# ORing_block.net
KiCad netlist of a schematic drawn in EAGLE
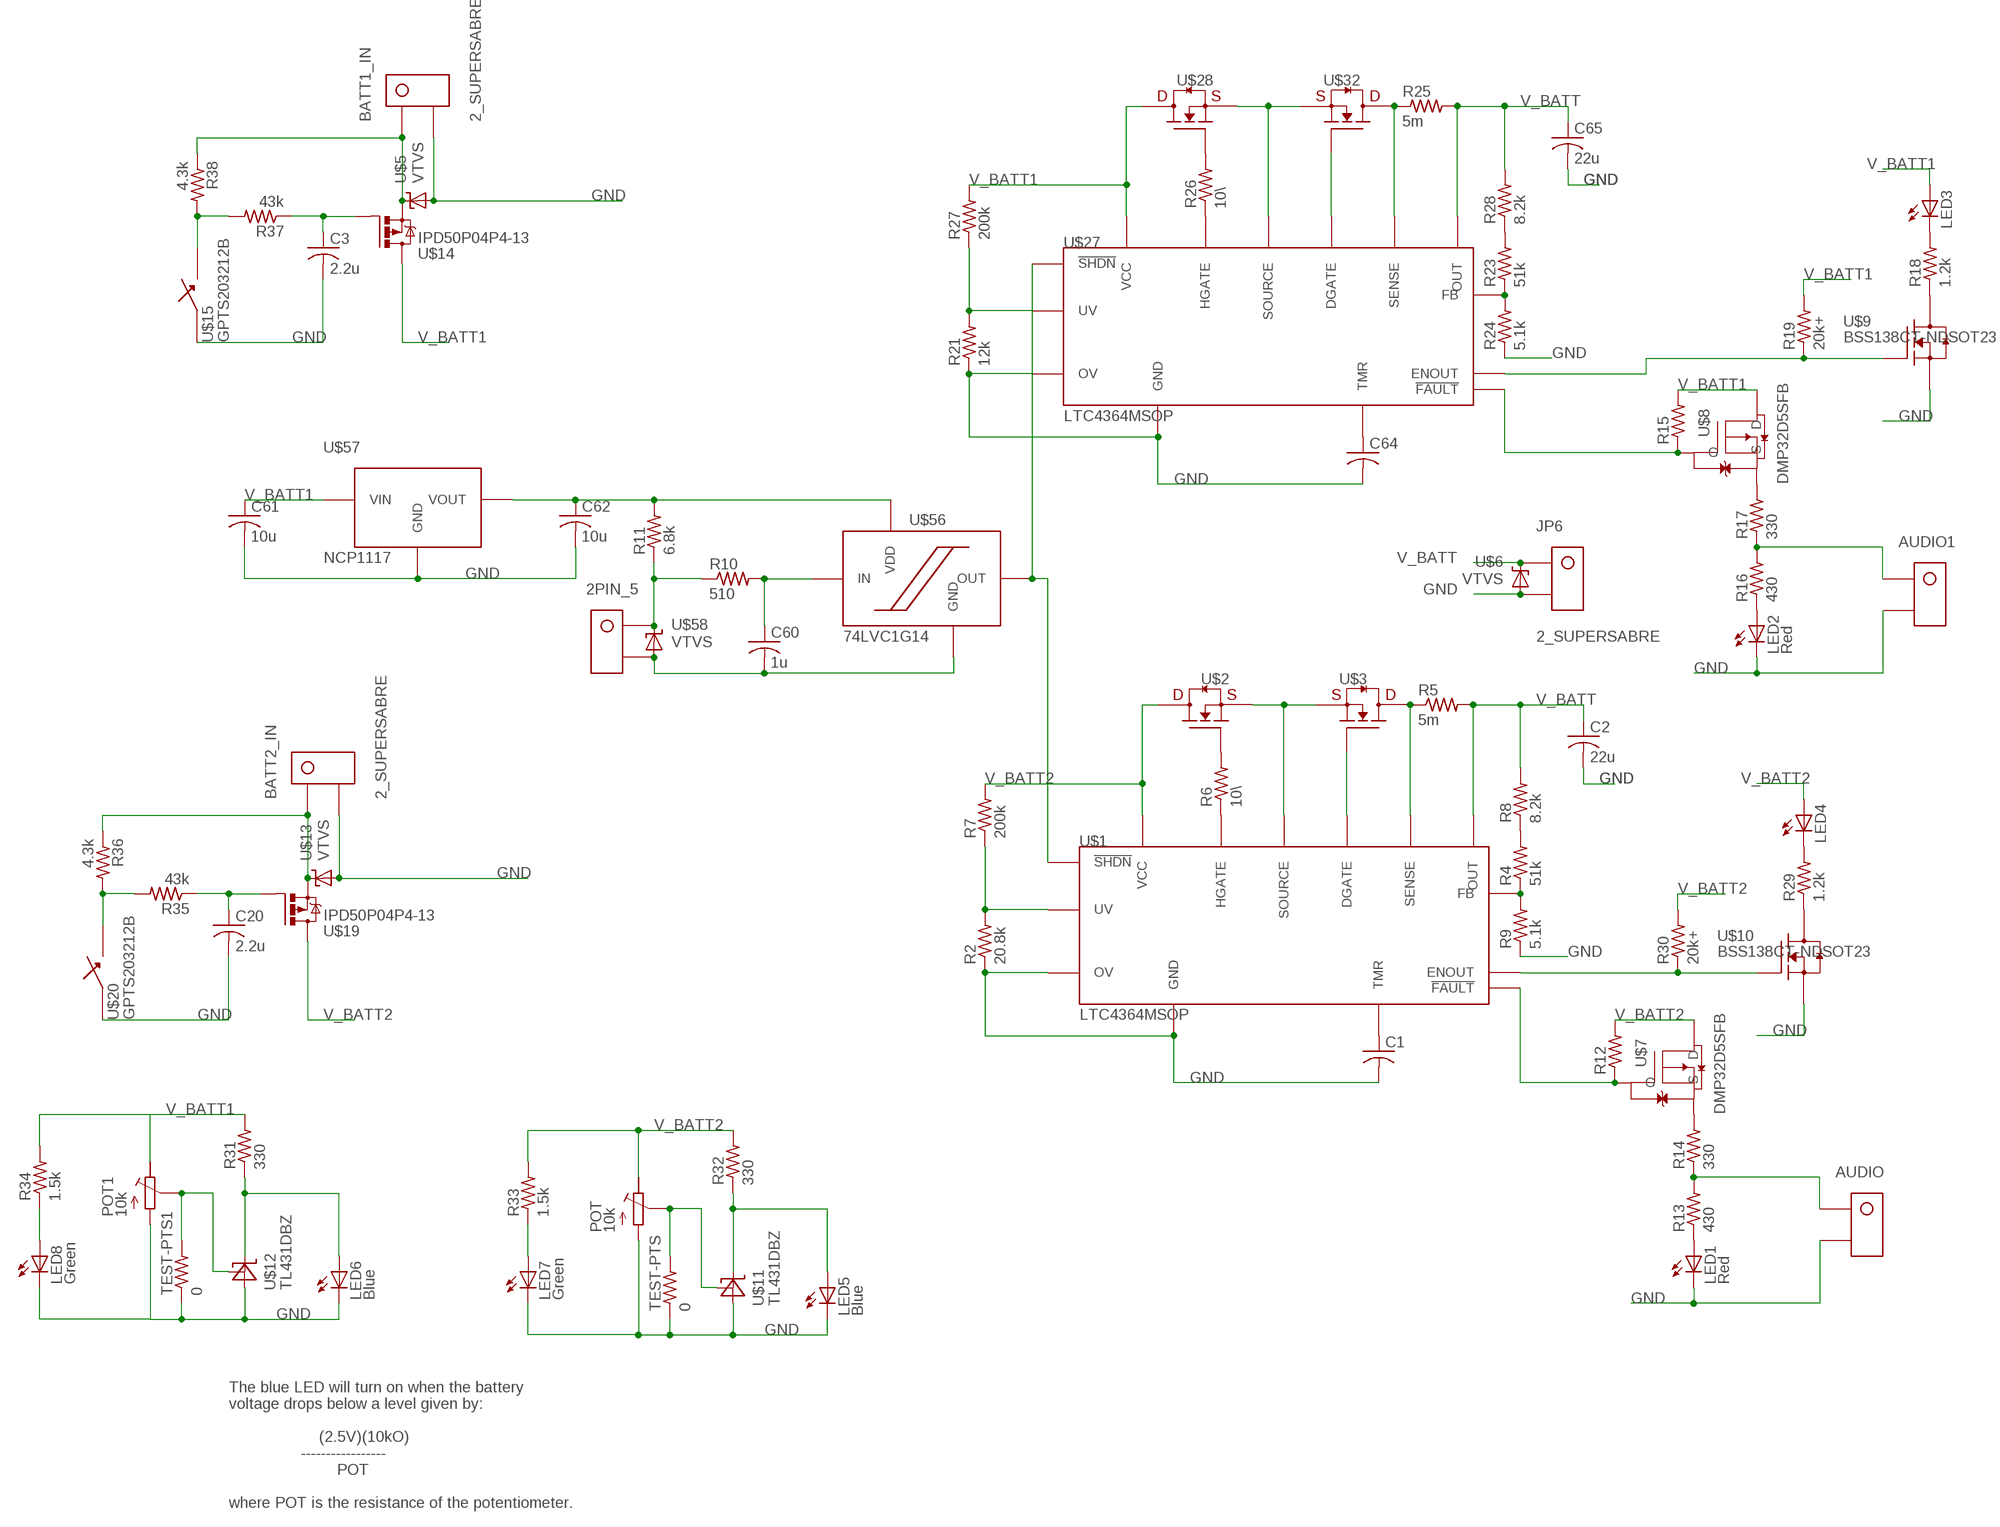
[diagram p0: schematic, sheet 1]

(export (version "E")
  (design (tool "Eeschema 10.0.6"))
  (components
    (comp (ref "2PIN_5")
      (value "KK254_VERT_2PIN22-29-2021")
      (footprint "eagle-import:KK254_VERT_2PIN")
      (libsource (lib "eagle-import") (part "KK254_VERT_2PIN22-29-2021"))
    )
    (comp (ref "AUDIO")
      (value "KK254_VERT_2PIN22-29-2021")
      (footprint "eagle-import:KK254_VERT_2PIN")
      (libsource (lib "eagle-import") (part "KK254_VERT_2PIN22-29-2021"))
    )
    (comp (ref "AUDIO1")
      (value "KK254_VERT_2PIN22-29-2021")
      (footprint "eagle-import:KK254_VERT_2PIN")
      (libsource (lib "eagle-import") (part "KK254_VERT_2PIN22-29-2021"))
    )
    (comp (ref "BATT1_IN")
      (value "2_SUPERSABRE")
      (footprint "eagle-import:SUPERSABRE_2CIRCUIT")
      (libsource (lib "eagle-import") (part "2_SUPERSABRE"))
    )
    (comp (ref "BATT2_IN")
      (value "2_SUPERSABRE")
      (footprint "eagle-import:SUPERSABRE_2CIRCUIT")
      (libsource (lib "eagle-import") (part "2_SUPERSABRE"))
    )
    (comp (ref "C1")
      (value "C-USC0805")
      (footprint "eagle-import:C0805")
      (libsource (lib "eagle-import") (part "C-USC0805"))
    )
    (comp (ref "C2")
      (value "22u")
      (footprint "eagle-import:C0805")
      (libsource (lib "eagle-import") (part "C-USC0805"))
    )
    (comp (ref "C3")
      (value "2.2u")
      (footprint "eagle-import:C0805")
      (libsource (lib "eagle-import") (part "C-USC0805"))
    )
    (comp (ref "C20")
      (value "2.2u")
      (footprint "eagle-import:C0805")
      (libsource (lib "eagle-import") (part "C-USC0805"))
    )
    (comp (ref "C60")
      (value "1u")
      (footprint "eagle-import:C0805")
      (libsource (lib "eagle-import") (part "C-USC0805"))
    )
    (comp (ref "C61")
      (value "10u")
      (footprint "eagle-import:C0805")
      (libsource (lib "eagle-import") (part "C-USC0805"))
    )
    (comp (ref "C62")
      (value "10u")
      (footprint "eagle-import:C0805")
      (libsource (lib "eagle-import") (part "C-USC0805"))
    )
    (comp (ref "C64")
      (value "C-USC0805")
      (footprint "eagle-import:C0805")
      (libsource (lib "eagle-import") (part "C-USC0805"))
    )
    (comp (ref "C65")
      (value "22u")
      (footprint "eagle-import:C0805")
      (libsource (lib "eagle-import") (part "C-USC0805"))
    )
    (comp (ref "JP6")
      (value "2_SUPERSABRE")
      (footprint "eagle-import:SUPERSABRE_2CIRCUIT")
      (libsource (lib "eagle-import") (part "2_SUPERSABRE"))
    )
    (comp (ref "LED1")
      (value "Red")
      (footprint "eagle-import:CHIPLED_0805")
      (libsource (lib "eagle-import") (part "LEDCHIPLED_0805"))
    )
    (comp (ref "LED2")
      (value "Red")
      (footprint "eagle-import:CHIPLED_0805")
      (libsource (lib "eagle-import") (part "LEDCHIPLED_0805"))
    )
    (comp (ref "LED3")
      (value "LEDCHIPLED_0805")
      (footprint "eagle-import:CHIPLED_0805")
      (libsource (lib "eagle-import") (part "LEDCHIPLED_0805"))
    )
    (comp (ref "LED4")
      (value "LEDCHIPLED_0805")
      (footprint "eagle-import:CHIPLED_0805")
      (libsource (lib "eagle-import") (part "LEDCHIPLED_0805"))
    )
    (comp (ref "LED5")
      (value "Blue")
      (footprint "eagle-import:0805")
      (libsource (lib "eagle-import") (part "0805_LED"))
    )
    (comp (ref "LED6")
      (value "Blue")
      (footprint "eagle-import:0805")
      (libsource (lib "eagle-import") (part "0805_LED"))
    )
    (comp (ref "LED7")
      (value "Green")
      (footprint "eagle-import:0805")
      (libsource (lib "eagle-import") (part "0805_LED"))
    )
    (comp (ref "LED8")
      (value "Green")
      (footprint "eagle-import:0805")
      (libsource (lib "eagle-import") (part "0805_LED"))
    )
    (comp (ref "POT")
      (value "10k")
      (footprint "eagle-import:PTV09A-4")
      (libsource (lib "eagle-import") (part "R-TRIMMPTV09A-4"))
    )
    (comp (ref "POT1")
      (value "10k")
      (footprint "eagle-import:PTV09A-4")
      (libsource (lib "eagle-import") (part "R-TRIMMPTV09A-4"))
    )
    (comp (ref "R2")
      (value "20.8k")
      (footprint "eagle-import:R0805")
      (libsource (lib "eagle-import") (part "R-US_R0805"))
    )
    (comp (ref "R4")
      (value "51k")
      (footprint "eagle-import:R0805")
      (libsource (lib "eagle-import") (part "R-US_R0805"))
    )
    (comp (ref "R5")
      (value "5m")
      (footprint "eagle-import:R0805")
      (libsource (lib "eagle-import") (part "R-US_R0805"))
    )
    (comp (ref "R6")
      (value "10\\")
      (footprint "eagle-import:R0805")
      (libsource (lib "eagle-import") (part "R-US_R0805"))
    )
    (comp (ref "R7")
      (value "200k")
      (footprint "eagle-import:R0805")
      (libsource (lib "eagle-import") (part "R-US_R0805"))
    )
    (comp (ref "R8")
      (value "8.2k")
      (footprint "eagle-import:R0805")
      (libsource (lib "eagle-import") (part "R-US_R0805"))
    )
    (comp (ref "R9")
      (value "5.1k")
      (footprint "eagle-import:R0805")
      (libsource (lib "eagle-import") (part "R-US_R0805"))
    )
    (comp (ref "R10")
      (value "510")
      (footprint "eagle-import:R0805")
      (libsource (lib "eagle-import") (part "R-US_R0805"))
    )
    (comp (ref "R11")
      (value "6.8k")
      (footprint "eagle-import:R0805")
      (libsource (lib "eagle-import") (part "R-US_R0805"))
    )
    (comp (ref "R12")
      (value "R-US_R0805")
      (footprint "eagle-import:R0805")
      (libsource (lib "eagle-import") (part "R-US_R0805"))
    )
    (comp (ref "R13")
      (value "430")
      (footprint "eagle-import:R0805")
      (libsource (lib "eagle-import") (part "R-US_R0805"))
    )
    (comp (ref "R14")
      (value "330")
      (footprint "eagle-import:R0805")
      (libsource (lib "eagle-import") (part "R-US_R0805"))
    )
    (comp (ref "R15")
      (value "R-US_R0805")
      (footprint "eagle-import:R0805")
      (libsource (lib "eagle-import") (part "R-US_R0805"))
    )
    (comp (ref "R16")
      (value "430")
      (footprint "eagle-import:R0805")
      (libsource (lib "eagle-import") (part "R-US_R0805"))
    )
    (comp (ref "R17")
      (value "330")
      (footprint "eagle-import:R0805")
      (libsource (lib "eagle-import") (part "R-US_R0805"))
    )
    (comp (ref "R18")
      (value "1.2k")
      (footprint "eagle-import:R0805")
      (libsource (lib "eagle-import") (part "R-US_R0805"))
    )
    (comp (ref "R19")
      (value "20k+")
      (footprint "eagle-import:R0805")
      (libsource (lib "eagle-import") (part "R-US_R0805"))
    )
    (comp (ref "R21")
      (value "12k")
      (footprint "eagle-import:R0805")
      (libsource (lib "eagle-import") (part "R-US_R0805"))
    )
    (comp (ref "R23")
      (value "51k")
      (footprint "eagle-import:R0805")
      (libsource (lib "eagle-import") (part "R-US_R0805"))
    )
    (comp (ref "R24")
      (value "5.1k")
      (footprint "eagle-import:R0805")
      (libsource (lib "eagle-import") (part "R-US_R0805"))
    )
    (comp (ref "R25")
      (value "5m")
      (footprint "eagle-import:R0805")
      (libsource (lib "eagle-import") (part "R-US_R0805"))
    )
    (comp (ref "R26")
      (value "10\\")
      (footprint "eagle-import:R0805")
      (libsource (lib "eagle-import") (part "R-US_R0805"))
    )
    (comp (ref "R27")
      (value "200k")
      (footprint "eagle-import:R0805")
      (libsource (lib "eagle-import") (part "R-US_R0805"))
    )
    (comp (ref "R28")
      (value "8.2k")
      (footprint "eagle-import:R0805")
      (libsource (lib "eagle-import") (part "R-US_R0805"))
    )
    (comp (ref "R29")
      (value "1.2k")
      (footprint "eagle-import:R0805")
      (libsource (lib "eagle-import") (part "R-US_R0805"))
    )
    (comp (ref "R30")
      (value "20k+")
      (footprint "eagle-import:R0805")
      (libsource (lib "eagle-import") (part "R-US_R0805"))
    )
    (comp (ref "R31")
      (value "330")
      (footprint "eagle-import:R0805")
      (libsource (lib "eagle-import") (part "R-US_R0805"))
    )
    (comp (ref "R32")
      (value "330")
      (footprint "eagle-import:R0805")
      (libsource (lib "eagle-import") (part "R-US_R0805"))
    )
    (comp (ref "R33")
      (value "1.5k")
      (footprint "eagle-import:R0805")
      (libsource (lib "eagle-import") (part "R-US_R0805"))
    )
    (comp (ref "R34")
      (value "1.5k")
      (footprint "eagle-import:R0805")
      (libsource (lib "eagle-import") (part "R-US_R0805"))
    )
    (comp (ref "R35")
      (value "43k")
      (footprint "eagle-import:R0805")
      (libsource (lib "eagle-import") (part "R-US_R0805"))
    )
    (comp (ref "R36")
      (value "4.3k")
      (footprint "eagle-import:R0805")
      (libsource (lib "eagle-import") (part "R-US_R0805"))
    )
    (comp (ref "R37")
      (value "43k")
      (footprint "eagle-import:R0805")
      (libsource (lib "eagle-import") (part "R-US_R0805"))
    )
    (comp (ref "R38")
      (value "4.3k")
      (footprint "eagle-import:R0805")
      (libsource (lib "eagle-import") (part "R-US_R0805"))
    )
    (comp (ref "TEST-PTS")
      (value "0")
      (footprint "eagle-import:V526-0")
      (libsource (lib "eagle-import") (part "R-US_V526-0"))
    )
    (comp (ref "TEST-PTS1")
      (value "0")
      (footprint "eagle-import:V526-0")
      (libsource (lib "eagle-import") (part "R-US_V526-0"))
    )
    (comp (ref "U$1")
      (value "LTC4364MSOP")
      (footprint "eagle-import:MSOP16")
      (libsource (lib "eagle-import") (part "LTC4364MSOP"))
    )
    (comp (ref "U$2")
      (value "FDMC8360LET40PWR33")
      (footprint "eagle-import:POWER33")
      (libsource (lib "eagle-import") (part "FDMC8360LET40PWR33"))
    )
    (comp (ref "U$3")
      (value "FDMC8360LET40PWR33")
      (footprint "eagle-import:POWER33")
      (libsource (lib "eagle-import") (part "FDMC8360LET40PWR33"))
    )
    (comp (ref "U$5")
      (value "VTVS")
      (footprint "eagle-import:DO-219AB")
      (libsource (lib "eagle-import") (part "VTVS"))
    )
    (comp (ref "U$6")
      (value "VTVS")
      (footprint "eagle-import:DO-219AB")
      (libsource (lib "eagle-import") (part "VTVS"))
    )
    (comp (ref "U$7")
      (value "DMP32D5SFB")
      (footprint "eagle-import:AP02002")
      (libsource (lib "eagle-import") (part "DMP32D5SFB"))
    )
    (comp (ref "U$8")
      (value "DMP32D5SFB")
      (footprint "eagle-import:AP02002")
      (libsource (lib "eagle-import") (part "DMP32D5SFB"))
    )
    (comp (ref "U$9")
      (value "BSS138CT-NDSOT23")
      (footprint "eagle-import:SOT23")
      (libsource (lib "eagle-import") (part "BSS138CT-NDSOT23"))
    )
    (comp (ref "U$10")
      (value "BSS138CT-NDSOT23")
      (footprint "eagle-import:SOT23")
      (libsource (lib "eagle-import") (part "BSS138CT-NDSOT23"))
    )
    (comp (ref "U$11")
      (value "TL431DBZ")
      (footprint "eagle-import:SOT-23-3")
      (libsource (lib "eagle-import") (part "TL431DBZ"))
    )
    (comp (ref "U$12")
      (value "TL431DBZ")
      (footprint "eagle-import:SOT-23-3")
      (libsource (lib "eagle-import") (part "TL431DBZ"))
    )
    (comp (ref "U$13")
      (value "VTVS")
      (footprint "eagle-import:DO-219AB")
      (libsource (lib "eagle-import") (part "VTVS"))
    )
    (comp (ref "U$14")
      (value "IPD50P04P4-13")
      (footprint "eagle-import:TO252-3")
      (libsource (lib "eagle-import") (part "IPD50P04P4-13"))
    )
    (comp (ref "U$15")
      (value "GPTS203212B")
      (footprint "eagle-import:GPTS203211B")
      (libsource (lib "eagle-import") (part "GPTS203212B"))
    )
    (comp (ref "U$19")
      (value "IPD50P04P4-13")
      (footprint "eagle-import:TO252-3")
      (libsource (lib "eagle-import") (part "IPD50P04P4-13"))
    )
    (comp (ref "U$20")
      (value "GPTS203212B")
      (footprint "eagle-import:GPTS203211B")
      (libsource (lib "eagle-import") (part "GPTS203212B"))
    )
    (comp (ref "U$27")
      (value "LTC4364MSOP")
      (footprint "eagle-import:MSOP16")
      (libsource (lib "eagle-import") (part "LTC4364MSOP"))
    )
    (comp (ref "U$28")
      (value "FDMC8360LET40PWR33")
      (footprint "eagle-import:POWER33")
      (libsource (lib "eagle-import") (part "FDMC8360LET40PWR33"))
    )
    (comp (ref "U$32")
      (value "FDMC8360LET40PWR33")
      (footprint "eagle-import:POWER33")
      (libsource (lib "eagle-import") (part "FDMC8360LET40PWR33"))
    )
    (comp (ref "U$56")
      (value "74LVC1G14")
      (footprint "eagle-import:TSSOP5")
      (libsource (lib "eagle-import") (part "74LVC1G14"))
    )
    (comp (ref "U$57")
      (value "NCP1117")
      (footprint "eagle-import:SOT-223")
      (libsource (lib "eagle-import") (part "NCP1117"))
    )
    (comp (ref "U$58")
      (value "VTVS")
      (footprint "eagle-import:DO-219AB")
      (libsource (lib "eagle-import") (part "VTVS"))
    )
  )
  (nets
    (net (code "1") (name "/GND") (class "Default")
      (node (ref "AUDIO") (pin "P$2") (pinfunction "P$2_P$2") (pintype "bidirectional"))
      (node (ref "AUDIO1") (pin "P$2") (pinfunction "P$2_P$2") (pintype "bidirectional"))
      (node (ref "BATT1_IN") (pin "P$2") (pinfunction "P$2_P$2") (pintype "bidirectional"))
      (node (ref "BATT2_IN") (pin "P$2") (pinfunction "P$2_P$2") (pintype "bidirectional"))
      (node (ref "C1") (pin "2") (pinfunction "2_2") (pintype "passive"))
      (node (ref "C2") (pin "2") (pinfunction "2_2") (pintype "passive"))
      (node (ref "C20") (pin "2") (pinfunction "2_2") (pintype "passive"))
      (node (ref "C3") (pin "2") (pinfunction "2_2") (pintype "passive"))
      (node (ref "C61") (pin "2") (pinfunction "2_2") (pintype "passive"))
      (node (ref "C62") (pin "2") (pinfunction "2_2") (pintype "passive"))
      (node (ref "C64") (pin "2") (pinfunction "2_2") (pintype "passive"))
      (node (ref "C65") (pin "2") (pinfunction "2_2") (pintype "passive"))
      (node (ref "JP6") (pin "P$2") (pinfunction "P$2_P$2") (pintype "bidirectional"))
      (node (ref "LED1") (pin "C") (pinfunction "C_C") (pintype "passive"))
      (node (ref "LED2") (pin "C") (pinfunction "C_C") (pintype "passive"))
      (node (ref "LED5") (pin "P$2") (pinfunction "C_P$2") (pintype "passive"))
      (node (ref "LED6") (pin "P$2") (pinfunction "C_P$2") (pintype "passive"))
      (node (ref "LED7") (pin "P$2") (pinfunction "C_P$2") (pintype "passive"))
      (node (ref "LED8") (pin "P$2") (pinfunction "C_P$2") (pintype "passive"))
      (node (ref "POT") (pin "P$3") (pinfunction "E_P$3") (pintype "passive"))
      (node (ref "POT1") (pin "P$3") (pinfunction "E_P$3") (pintype "passive"))
      (node (ref "R2") (pin "1") (pinfunction "1_1") (pintype "passive"))
      (node (ref "R21") (pin "1") (pinfunction "1_1") (pintype "passive"))
      (node (ref "R24") (pin "1") (pinfunction "1_1") (pintype "passive"))
      (node (ref "R9") (pin "1") (pinfunction "1_1") (pintype "passive"))
      (node (ref "TEST-PTS") (pin "1") (pinfunction "1_1") (pintype "passive"))
      (node (ref "TEST-PTS1") (pin "1") (pinfunction "1_1") (pintype "passive"))
      (node (ref "U$1") (pin "GND") (pinfunction "GND_GND") (pintype "bidirectional"))
      (node (ref "U$1") (pin "OV") (pinfunction "OV_OV") (pintype "bidirectional"))
      (node (ref "U$10") (pin "2") (pinfunction "S_2") (pintype "passive"))
      (node (ref "U$11") (pin "P$3") (pinfunction "A_P$3") (pintype "passive"))
      (node (ref "U$12") (pin "P$3") (pinfunction "A_P$3") (pintype "passive"))
      (node (ref "U$13") (pin "P$1") (pinfunction "A_P$1") (pintype "passive"))
      (node (ref "U$15") (pin "P$1") (pinfunction "P$1_P$1") (pintype "bidirectional"))
      (node (ref "U$20") (pin "P$1") (pinfunction "P$1_P$1") (pintype "bidirectional"))
      (node (ref "U$27") (pin "GND") (pinfunction "GND_GND") (pintype "bidirectional"))
      (node (ref "U$27") (pin "OV") (pinfunction "OV_OV") (pintype "bidirectional"))
      (node (ref "U$5") (pin "P$1") (pinfunction "A_P$1") (pintype "passive"))
      (node (ref "U$57") (pin "P$1") (pinfunction "GND_P$1") (pintype "bidirectional"))
      (node (ref "U$6") (pin "P$1") (pinfunction "A_P$1") (pintype "passive"))
      (node (ref "U$9") (pin "2") (pinfunction "S_2") (pintype "passive"))
    )
    (net (code "2") (name "/V_BATT") (class "Default")
      (node (ref "C2") (pin "1") (pinfunction "1_1") (pintype "passive"))
      (node (ref "C65") (pin "1") (pinfunction "1_1") (pintype "passive"))
      (node (ref "JP6") (pin "P$1") (pinfunction "P$1_P$1") (pintype "bidirectional"))
      (node (ref "R25") (pin "2") (pinfunction "2_2") (pintype "passive"))
      (node (ref "R28") (pin "2") (pinfunction "2_2") (pintype "passive"))
      (node (ref "R5") (pin "2") (pinfunction "2_2") (pintype "passive"))
      (node (ref "R8") (pin "2") (pinfunction "2_2") (pintype "passive"))
      (node (ref "U$1") (pin "OUT") (pinfunction "OUT_OUT") (pintype "bidirectional"))
      (node (ref "U$27") (pin "OUT") (pinfunction "OUT_OUT") (pintype "bidirectional"))
      (node (ref "U$6") (pin "P$2") (pinfunction "C_P$2") (pintype "passive"))
    )
    (net (code "3") (name "/V_BATT1") (class "Default")
      (node (ref "C61") (pin "1") (pinfunction "1_1") (pintype "passive"))
      (node (ref "LED3") (pin "A") (pinfunction "A_A") (pintype "passive"))
      (node (ref "POT1") (pin "P$1") (pinfunction "A_P$1") (pintype "passive"))
      (node (ref "R15") (pin "2") (pinfunction "2_2") (pintype "passive"))
      (node (ref "R19") (pin "2") (pinfunction "2_2") (pintype "passive"))
      (node (ref "R27") (pin "2") (pinfunction "2_2") (pintype "passive"))
      (node (ref "R31") (pin "2") (pinfunction "2_2") (pintype "passive"))
      (node (ref "R34") (pin "2") (pinfunction "2_2") (pintype "passive"))
      (node (ref "U$14") (pin "3") (pinfunction "S_3") (pintype "passive"))
      (node (ref "U$27") (pin "VCC") (pinfunction "VCC_VCC") (pintype "bidirectional"))
      (node (ref "U$28") (pin "DRAIN") (pinfunction "DRAIN_DRAIN") (pintype "bidirectional"))
      (node (ref "U$57") (pin "P$3") (pinfunction "VIN_P$3") (pintype "bidirectional"))
      (node (ref "U$8") (pin "P$3") (pinfunction "D_P$3") (pintype "bidirectional"))
    )
    (net (code "4") (name "/V_BATT2") (class "Default")
      (node (ref "LED4") (pin "A") (pinfunction "A_A") (pintype "passive"))
      (node (ref "POT") (pin "P$1") (pinfunction "A_P$1") (pintype "passive"))
      (node (ref "R12") (pin "2") (pinfunction "2_2") (pintype "passive"))
      (node (ref "R30") (pin "2") (pinfunction "2_2") (pintype "passive"))
      (node (ref "R32") (pin "2") (pinfunction "2_2") (pintype "passive"))
      (node (ref "R33") (pin "2") (pinfunction "2_2") (pintype "passive"))
      (node (ref "R7") (pin "2") (pinfunction "2_2") (pintype "passive"))
      (node (ref "U$1") (pin "VCC") (pinfunction "VCC_VCC") (pintype "bidirectional"))
      (node (ref "U$19") (pin "3") (pinfunction "S_3") (pintype "passive"))
      (node (ref "U$2") (pin "DRAIN") (pinfunction "DRAIN_DRAIN") (pintype "bidirectional"))
      (node (ref "U$7") (pin "P$3") (pinfunction "D_P$3") (pintype "bidirectional"))
    )
    (net (code "5") (name "Net-(AUDIO-PadP$1)") (class "Default")
      (node (ref "AUDIO") (pin "P$1") (pinfunction "P$1_P$1") (pintype "bidirectional"))
      (node (ref "R13") (pin "2") (pinfunction "2_2") (pintype "passive"))
      (node (ref "R14") (pin "1") (pinfunction "1_1") (pintype "passive"))
    )
    (net (code "6") (name "Net-(AUDIO1-PadP$1)") (class "Default")
      (node (ref "AUDIO1") (pin "P$1") (pinfunction "P$1_P$1") (pintype "bidirectional"))
      (node (ref "R16") (pin "2") (pinfunction "2_2") (pintype "passive"))
      (node (ref "R17") (pin "1") (pinfunction "1_1") (pintype "passive"))
    )
    (net (code "7") (name "Net-(C1-Pad1)") (class "Default")
      (node (ref "C1") (pin "1") (pinfunction "1_1") (pintype "passive"))
      (node (ref "U$1") (pin "TMR") (pinfunction "TMR_TMR") (pintype "bidirectional"))
    )
    (net (code "8") (name "Net-(C64-Pad1)") (class "Default")
      (node (ref "C64") (pin "1") (pinfunction "1_1") (pintype "passive"))
      (node (ref "U$27") (pin "TMR") (pinfunction "TMR_TMR") (pintype "bidirectional"))
    )
    (net (code "9") (name "Net-(LED1-PadA)") (class "Default")
      (node (ref "LED1") (pin "A") (pinfunction "A_A") (pintype "passive"))
      (node (ref "R13") (pin "1") (pinfunction "1_1") (pintype "passive"))
    )
    (net (code "10") (name "Net-(LED2-PadA)") (class "Default")
      (node (ref "LED2") (pin "A") (pinfunction "A_A") (pintype "passive"))
      (node (ref "R16") (pin "1") (pinfunction "1_1") (pintype "passive"))
    )
    (net (code "11") (name "Net-(LED3-PadC)") (class "Default")
      (node (ref "LED3") (pin "C") (pinfunction "C_C") (pintype "passive"))
      (node (ref "R18") (pin "2") (pinfunction "2_2") (pintype "passive"))
    )
    (net (code "12") (name "Net-(LED4-PadC)") (class "Default")
      (node (ref "LED4") (pin "C") (pinfunction "C_C") (pintype "passive"))
      (node (ref "R29") (pin "2") (pinfunction "2_2") (pintype "passive"))
    )
    (net (code "13") (name "Net-(LED5-A)") (class "Default")
      (node (ref "LED5") (pin "P$1") (pinfunction "A_P$1") (pintype "passive"))
      (node (ref "R32") (pin "1") (pinfunction "1_1") (pintype "passive"))
      (node (ref "U$11") (pin "P$1") (pinfunction "C_P$1") (pintype "passive"))
    )
    (net (code "14") (name "Net-(LED6-A)") (class "Default")
      (node (ref "LED6") (pin "P$1") (pinfunction "A_P$1") (pintype "passive"))
      (node (ref "R31") (pin "1") (pinfunction "1_1") (pintype "passive"))
      (node (ref "U$12") (pin "P$1") (pinfunction "C_P$1") (pintype "passive"))
    )
    (net (code "15") (name "Net-(LED7-A)") (class "Default")
      (node (ref "LED7") (pin "P$1") (pinfunction "A_P$1") (pintype "passive"))
      (node (ref "R33") (pin "1") (pinfunction "1_1") (pintype "passive"))
    )
    (net (code "16") (name "Net-(LED8-A)") (class "Default")
      (node (ref "LED8") (pin "P$1") (pinfunction "A_P$1") (pintype "passive"))
      (node (ref "R34") (pin "1") (pinfunction "1_1") (pintype "passive"))
    )
    (net (code "17") (name "Net-(POT-S)") (class "Default")
      (node (ref "POT") (pin "P$2") (pinfunction "S_P$2") (pintype "passive"))
      (node (ref "TEST-PTS") (pin "2") (pinfunction "2_2") (pintype "passive"))
      (node (ref "U$11") (pin "P$2") (pinfunction "REF_P$2") (pintype "bidirectional"))
    )
    (net (code "18") (name "Net-(POT1-S)") (class "Default")
      (node (ref "POT1") (pin "P$2") (pinfunction "S_P$2") (pintype "passive"))
      (node (ref "TEST-PTS1") (pin "2") (pinfunction "2_2") (pintype "passive"))
      (node (ref "U$12") (pin "P$2") (pinfunction "REF_P$2") (pintype "bidirectional"))
    )
    (net (code "19") (name "Net-(R2-Pad2)") (class "Default")
      (node (ref "R2") (pin "2") (pinfunction "2_2") (pintype "passive"))
      (node (ref "R7") (pin "1") (pinfunction "1_1") (pintype "passive"))
      (node (ref "U$1") (pin "UV") (pinfunction "UV_UV") (pintype "bidirectional"))
    )
    (net (code "20") (name "Net-(R4-Pad1)") (class "Default")
      (node (ref "R4") (pin "1") (pinfunction "1_1") (pintype "passive"))
      (node (ref "R9") (pin "2") (pinfunction "2_2") (pintype "passive"))
      (node (ref "U$1") (pin "FB") (pinfunction "FB_FB") (pintype "bidirectional"))
    )
    (net (code "21") (name "Net-(R4-Pad2)") (class "Default")
      (node (ref "R4") (pin "2") (pinfunction "2_2") (pintype "passive"))
      (node (ref "R8") (pin "1") (pinfunction "1_1") (pintype "passive"))
    )
    (net (code "22") (name "Net-(R5-Pad1)") (class "Default")
      (node (ref "R5") (pin "1") (pinfunction "1_1") (pintype "passive"))
      (node (ref "U$1") (pin "SENSE") (pinfunction "SENSE_SENSE") (pintype "bidirectional"))
      (node (ref "U$3") (pin "DRAIN") (pinfunction "DRAIN_DRAIN") (pintype "bidirectional"))
    )
    (net (code "23") (name "Net-(R6-Pad1)") (class "Default")
      (node (ref "R6") (pin "1") (pinfunction "1_1") (pintype "passive"))
      (node (ref "U$1") (pin "HGATE") (pinfunction "HGATE_HGATE") (pintype "bidirectional"))
    )
    (net (code "24") (name "Net-(R6-Pad2)") (class "Default")
      (node (ref "R6") (pin "2") (pinfunction "2_2") (pintype "passive"))
      (node (ref "U$2") (pin "GATE") (pinfunction "GATE_GATE") (pintype "passive"))
    )
    (net (code "25") (name "Net-(R21-Pad2)") (class "Default")
      (node (ref "R21") (pin "2") (pinfunction "2_2") (pintype "passive"))
      (node (ref "R27") (pin "1") (pinfunction "1_1") (pintype "passive"))
      (node (ref "U$27") (pin "UV") (pinfunction "UV_UV") (pintype "bidirectional"))
    )
    (net (code "26") (name "Net-(R23-Pad1)") (class "Default")
      (node (ref "R23") (pin "1") (pinfunction "1_1") (pintype "passive"))
      (node (ref "R24") (pin "2") (pinfunction "2_2") (pintype "passive"))
      (node (ref "U$27") (pin "FB") (pinfunction "FB_FB") (pintype "bidirectional"))
    )
    (net (code "27") (name "Net-(R23-Pad2)") (class "Default")
      (node (ref "R23") (pin "2") (pinfunction "2_2") (pintype "passive"))
      (node (ref "R28") (pin "1") (pinfunction "1_1") (pintype "passive"))
    )
    (net (code "28") (name "Net-(R25-Pad1)") (class "Default")
      (node (ref "R25") (pin "1") (pinfunction "1_1") (pintype "passive"))
      (node (ref "U$27") (pin "SENSE") (pinfunction "SENSE_SENSE") (pintype "bidirectional"))
      (node (ref "U$32") (pin "DRAIN") (pinfunction "DRAIN_DRAIN") (pintype "bidirectional"))
    )
    (net (code "29") (name "Net-(R26-Pad1)") (class "Default")
      (node (ref "R26") (pin "1") (pinfunction "1_1") (pintype "passive"))
      (node (ref "U$27") (pin "HGATE") (pinfunction "HGATE_HGATE") (pintype "bidirectional"))
    )
    (net (code "30") (name "Net-(R26-Pad2)") (class "Default")
      (node (ref "R26") (pin "2") (pinfunction "2_2") (pintype "passive"))
      (node (ref "U$28") (pin "GATE") (pinfunction "GATE_GATE") (pintype "passive"))
    )
    (net (code "31") (name "Net-(R35-Pad2)") (class "Default")
      (node (ref "R35") (pin "2") (pinfunction "2_2") (pintype "passive"))
      (node (ref "R36") (pin "2") (pinfunction "2_2") (pintype "passive"))
      (node (ref "U$20") (pin "P$2") (pinfunction "P$2_P$2") (pintype "bidirectional"))
    )
    (net (code "32") (name "Net-(R37-Pad2)") (class "Default")
      (node (ref "R37") (pin "2") (pinfunction "2_2") (pintype "passive"))
      (node (ref "R38") (pin "2") (pinfunction "2_2") (pintype "passive"))
      (node (ref "U$15") (pin "P$2") (pinfunction "P$2_P$2") (pintype "bidirectional"))
    )
    (net (code "33") (name "Net-(U$1-PadDGATE)") (class "Default")
      (node (ref "U$1") (pin "DGATE") (pinfunction "DGATE_DGATE") (pintype "bidirectional"))
      (node (ref "U$3") (pin "GATE") (pinfunction "GATE_GATE") (pintype "passive"))
    )
    (net (code "34") (name "Net-(U$1-PadSOURCE)") (class "Default")
      (node (ref "U$1") (pin "SOURCE") (pinfunction "SOURCE_SOURCE") (pintype "bidirectional"))
      (node (ref "U$2") (pin "SOURCE1") (pinfunction "SOURCE_SOURCE1") (pintype "passive"))
      (node (ref "U$2") (pin "SOURCE2") (pinfunction "SOURCE_SOURCE2") (pintype "passive"))
      (node (ref "U$2") (pin "SOURCE3") (pinfunction "SOURCE_SOURCE3") (pintype "passive"))
      (node (ref "U$3") (pin "SOURCE1") (pinfunction "SOURCE_SOURCE1") (pintype "passive"))
      (node (ref "U$3") (pin "SOURCE2") (pinfunction "SOURCE_SOURCE2") (pintype "passive"))
      (node (ref "U$3") (pin "SOURCE3") (pinfunction "SOURCE_SOURCE3") (pintype "passive"))
    )
    (net (code "35") (name "Net-(U$1-~{FAULT})") (class "Default")
      (node (ref "R12") (pin "1") (pinfunction "1_1") (pintype "passive"))
      (node (ref "U$1") (pin "FLT") (pinfunction "~{FAULT}_FLT") (pintype "bidirectional"))
      (node (ref "U$7") (pin "P$2") (pinfunction "G_P$2") (pintype "bidirectional"))
    )
    (net (code "36") (name "Net-(U$1-~{SHDN})") (class "Default")
      (node (ref "U$1") (pin "SHDN") (pinfunction "~{SHDN}_SHDN") (pintype "bidirectional"))
      (node (ref "U$27") (pin "SHDN") (pinfunction "~{SHDN}_SHDN") (pintype "bidirectional"))
      (node (ref "U$56") (pin "P$4") (pinfunction "OUT_P$4") (pintype "bidirectional"))
    )
    (net (code "37") (name "Net-(U$7-S)") (class "Default")
      (node (ref "R14") (pin "2") (pinfunction "2_2") (pintype "passive"))
      (node (ref "U$7") (pin "P$1") (pinfunction "S_P$1") (pintype "bidirectional"))
    )
    (net (code "38") (name "Net-(U$8-S)") (class "Default")
      (node (ref "R17") (pin "2") (pinfunction "2_2") (pintype "passive"))
      (node (ref "U$8") (pin "P$1") (pinfunction "S_P$1") (pintype "bidirectional"))
    )
    (net (code "39") (name "Net-(U$9-D)") (class "Default")
      (node (ref "R18") (pin "1") (pinfunction "1_1") (pintype "passive"))
      (node (ref "U$9") (pin "3") (pinfunction "D_3") (pintype "bidirectional"))
    )
    (net (code "40") (name "Net-(U$9-G)") (class "Default")
      (node (ref "R19") (pin "1") (pinfunction "1_1") (pintype "passive"))
      (node (ref "U$27") (pin "ENOUT") (pinfunction "ENOUT_ENOUT") (pintype "bidirectional"))
      (node (ref "U$9") (pin "1") (pinfunction "G_1") (pintype "passive"))
    )
    (net (code "41") (name "Net-(U$10-D)") (class "Default")
      (node (ref "R29") (pin "1") (pinfunction "1_1") (pintype "passive"))
      (node (ref "U$10") (pin "3") (pinfunction "D_3") (pintype "bidirectional"))
    )
    (net (code "42") (name "Net-(U$10-G)") (class "Default")
      (node (ref "R30") (pin "1") (pinfunction "1_1") (pintype "passive"))
      (node (ref "U$1") (pin "ENOUT") (pinfunction "ENOUT_ENOUT") (pintype "bidirectional"))
      (node (ref "U$10") (pin "1") (pinfunction "G_1") (pintype "passive"))
    )
    (net (code "43") (name "Net-(U$13-C)") (class "Default")
      (node (ref "BATT2_IN") (pin "P$1") (pinfunction "P$1_P$1") (pintype "bidirectional"))
      (node (ref "R36") (pin "1") (pinfunction "1_1") (pintype "passive"))
      (node (ref "U$13") (pin "P$2") (pinfunction "C_P$2") (pintype "passive"))
      (node (ref "U$19") (pin "TAB") (pinfunction "D_TAB") (pintype "passive"))
    )
    (net (code "44") (name "Net-(U$14-D)") (class "Default")
      (node (ref "BATT1_IN") (pin "P$1") (pinfunction "P$1_P$1") (pintype "bidirectional"))
      (node (ref "R38") (pin "1") (pinfunction "1_1") (pintype "passive"))
      (node (ref "U$14") (pin "TAB") (pinfunction "D_TAB") (pintype "passive"))
      (node (ref "U$5") (pin "P$2") (pinfunction "C_P$2") (pintype "passive"))
    )
    (net (code "45") (name "Net-(U$14-G)") (class "Default")
      (node (ref "C3") (pin "1") (pinfunction "1_1") (pintype "passive"))
      (node (ref "R37") (pin "1") (pinfunction "1_1") (pintype "passive"))
      (node (ref "U$14") (pin "1") (pinfunction "G_1") (pintype "passive"))
    )
    (net (code "46") (name "Net-(U$19-G)") (class "Default")
      (node (ref "C20") (pin "1") (pinfunction "1_1") (pintype "passive"))
      (node (ref "R35") (pin "1") (pinfunction "1_1") (pintype "passive"))
      (node (ref "U$19") (pin "1") (pinfunction "G_1") (pintype "passive"))
    )
    (net (code "47") (name "Net-(U$27-PadDGATE)") (class "Default")
      (node (ref "U$27") (pin "DGATE") (pinfunction "DGATE_DGATE") (pintype "bidirectional"))
      (node (ref "U$32") (pin "GATE") (pinfunction "GATE_GATE") (pintype "passive"))
    )
    (net (code "48") (name "Net-(U$27-PadSOURCE)") (class "Default")
      (node (ref "U$27") (pin "SOURCE") (pinfunction "SOURCE_SOURCE") (pintype "bidirectional"))
      (node (ref "U$28") (pin "SOURCE1") (pinfunction "SOURCE_SOURCE1") (pintype "passive"))
      (node (ref "U$28") (pin "SOURCE2") (pinfunction "SOURCE_SOURCE2") (pintype "passive"))
      (node (ref "U$28") (pin "SOURCE3") (pinfunction "SOURCE_SOURCE3") (pintype "passive"))
      (node (ref "U$32") (pin "SOURCE1") (pinfunction "SOURCE_SOURCE1") (pintype "passive"))
      (node (ref "U$32") (pin "SOURCE2") (pinfunction "SOURCE_SOURCE2") (pintype "passive"))
      (node (ref "U$32") (pin "SOURCE3") (pinfunction "SOURCE_SOURCE3") (pintype "passive"))
    )
    (net (code "49") (name "Net-(U$27-~{FAULT})") (class "Default")
      (node (ref "R15") (pin "1") (pinfunction "1_1") (pintype "passive"))
      (node (ref "U$27") (pin "FLT") (pinfunction "~{FAULT}_FLT") (pintype "bidirectional"))
      (node (ref "U$8") (pin "P$2") (pinfunction "G_P$2") (pintype "bidirectional"))
    )
    (net (code "50") (name "Net-(U$56-GND)") (class "Default")
      (node (ref "2PIN_5") (pin "P$2") (pinfunction "P$2_P$2") (pintype "bidirectional"))
      (node (ref "C60") (pin "2") (pinfunction "2_2") (pintype "passive"))
      (node (ref "U$56") (pin "P$3") (pinfunction "GND_P$3") (pintype "bidirectional"))
      (node (ref "U$58") (pin "P$1") (pinfunction "A_P$1") (pintype "passive"))
    )
    (net (code "51") (name "Net-(U$56-IN)") (class "Default")
      (node (ref "C60") (pin "1") (pinfunction "1_1") (pintype "passive"))
      (node (ref "R10") (pin "2") (pinfunction "2_2") (pintype "passive"))
      (node (ref "U$56") (pin "P$2") (pinfunction "IN_P$2") (pintype "bidirectional"))
    )
    (net (code "52") (name "Net-(U$56-VDD)") (class "Default")
      (node (ref "C62") (pin "1") (pinfunction "1_1") (pintype "passive"))
      (node (ref "R11") (pin "2") (pinfunction "2_2") (pintype "passive"))
      (node (ref "U$56") (pin "P$5") (pinfunction "VDD_P$5") (pintype "bidirectional"))
      (node (ref "U$57") (pin "P$2") (pinfunction "VOUT_P$2") (pintype "bidirectional"))
      (node (ref "U$57") (pin "P$4") (pinfunction "VOUT_P$4") (pintype "bidirectional"))
    )
    (net (code "53") (name "Net-(U$58-C)") (class "Default")
      (node (ref "2PIN_5") (pin "P$1") (pinfunction "P$1_P$1") (pintype "bidirectional"))
      (node (ref "R10") (pin "1") (pinfunction "1_1") (pintype "passive"))
      (node (ref "R11") (pin "1") (pinfunction "1_1") (pintype "passive"))
      (node (ref "U$58") (pin "P$2") (pinfunction "C_P$2") (pintype "passive"))
    )
  )
)
